# power_phase.net
KiCad netlist of a schematic drawn in Altium Designer
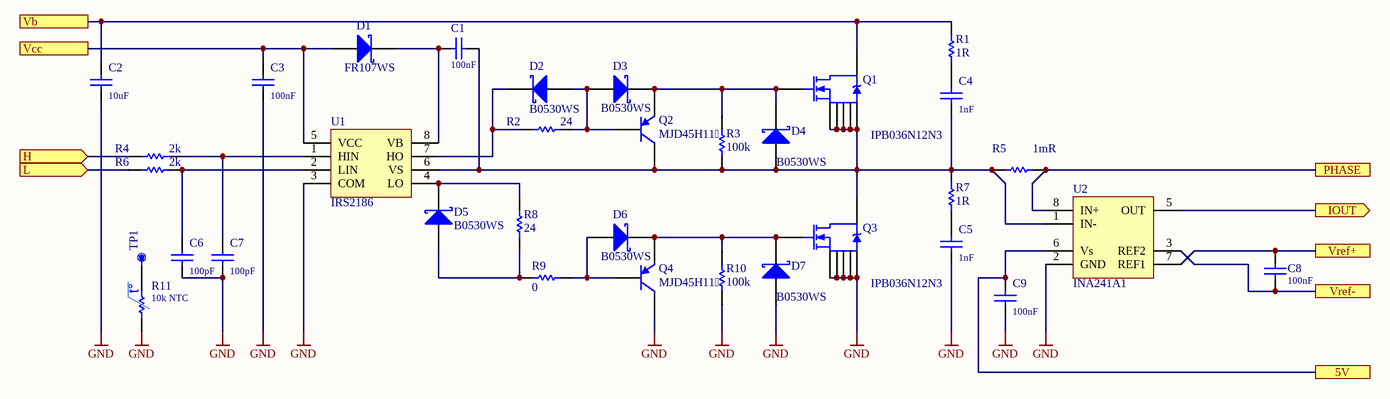
[diagram p0: power_phase.schdoc]

(export (version "E")
  (design (tool "Eeschema 10.0.6"))
  (components
    (comp (ref "C1")
      (value "100nF")
      (footprint "C0805_L")
      (description "100n 0805")
      (libsource (lib "Miscellaneous Devices") (part "CAP"))
    )
    (comp (ref "C2")
      (value "10uF")
      (footprint "C2220")
      (description "10uF 100V 2220")
      (libsource (lib "Miscellaneous Devices") (part "CAP"))
    )
    (comp (ref "C3")
      (value "100nF")
      (footprint "C0603")
      (description "100n 0603")
      (libsource (lib "Miscellaneous Devices") (part "CAP"))
    )
    (comp (ref "C4")
      (value "1nF")
      (footprint "C0805")
      (description "1nF 100V 0805")
      (libsource (lib "Miscellaneous Devices") (part "CAP"))
    )
    (comp (ref "C5")
      (value "1nF")
      (footprint "C0805")
      (description "1nF 100V 0805")
      (libsource (lib "Miscellaneous Devices") (part "CAP"))
    )
    (comp (ref "C6")
      (value "100pF")
      (footprint "C0402")
      (description "100pF 0402")
      (libsource (lib "Miscellaneous Devices") (part "CAP"))
    )
    (comp (ref "C7")
      (value "100pF")
      (footprint "C0402")
      (description "100pF 0402")
      (libsource (lib "Miscellaneous Devices") (part "CAP"))
    )
    (comp (ref "C8")
      (value "100nF")
      (footprint "C0402")
      (description "100nF 0402")
      (libsource (lib "Miscellaneous Devices") (part "CAP"))
    )
    (comp (ref "C9")
      (value "100nF")
      (footprint "C0402")
      (description "100nF 0402")
      (libsource (lib "Miscellaneous Devices") (part "CAP"))
    )
    (comp (ref "D1")
      (value "FR107WS")
      (footprint "SOD-323")
      (libsource (lib "Miscellaneous Devices") (part "Diode 10TQ035_1"))
    )
    (comp (ref "D2")
      (value "B0530WS")
      (footprint "SOD-323")
      (description "FR107WS")
      (libsource (lib "Miscellaneous Devices") (part "Diode 10TQ035_1"))
    )
    (comp (ref "D3")
      (value "B0530WS")
      (footprint "SOD-323")
      (description "FR107WS")
      (libsource (lib "Miscellaneous Devices") (part "Diode 10TQ035_1"))
    )
    (comp (ref "D4")
      (value "B0530WS")
      (footprint "SOD-323")
      (description "FR107WS")
      (libsource (lib "Miscellaneous Devices") (part "Diode 10TQ035_1"))
    )
    (comp (ref "D5")
      (value "B0530WS")
      (footprint "SOD-323")
      (description "FR107WS")
      (libsource (lib "Miscellaneous Devices") (part "Diode 10TQ035_1"))
    )
    (comp (ref "D6")
      (value "B0530WS")
      (footprint "SOD-323")
      (description "FR107WS")
      (libsource (lib "Miscellaneous Devices") (part "Diode 10TQ035_1"))
    )
    (comp (ref "D7")
      (value "B0530WS")
      (footprint "SOD-323")
      (description "FR107WS")
      (libsource (lib "Miscellaneous Devices") (part "Diode 10TQ035_1"))
    )
    (comp (ref "Q1")
      (value "IPB036N12N3")
      (footprint "TO-263-7")
      (description "IPB036N12N3GATMA1")
      (libsource (lib "Miscellaneous Devices") (part "NMOS-2"))
    )
    (comp (ref "Q2")
      (value "MJD45H11")
      (footprint "TO-252AA")
      (libsource (lib "Miscellaneous Devices") (part "PNP"))
    )
    (comp (ref "Q3")
      (value "IPB036N12N3")
      (footprint "TO-263-7")
      (description "IPB036N12N3GATMA1")
      (libsource (lib "Miscellaneous Devices") (part "NMOS-2"))
    )
    (comp (ref "Q4")
      (value "MJD45H11")
      (footprint "TO-252AA")
      (libsource (lib "Miscellaneous Devices") (part "PNP"))
    )
    (comp (ref "R1")
      (value "1R")
      (footprint "R1206")
      (description "1R 1206")
      (libsource (lib "Miscellaneous Devices") (part "Res1"))
    )
    (comp (ref "R2")
      (value "24")
      (footprint "R0603")
      (description "24R 0603")
      (libsource (lib "Miscellaneous Devices") (part "Res1"))
    )
    (comp (ref "R3")
      (value "100k")
      (footprint "R0805")
      (description "100k 0805")
      (libsource (lib "Miscellaneous Devices") (part "Res1"))
    )
    (comp (ref "R4")
      (value "2k")
      (footprint "R0603")
      (description "2k 0603")
      (libsource (lib "Miscellaneous Devices") (part "Res1"))
    )
    (comp (ref "R5")
      (value "1mR")
      (footprint "RES_CSS2H-3920R")
      (libsource (lib "Miscellaneous Devices") (part "Res1"))
    )
    (comp (ref "R6")
      (value "2k")
      (footprint "R0603")
      (description "2k 0603")
      (libsource (lib "Miscellaneous Devices") (part "Res1"))
    )
    (comp (ref "R7")
      (value "1R")
      (footprint "R1206")
      (description "1R 1206")
      (libsource (lib "Miscellaneous Devices") (part "Res1"))
    )
    (comp (ref "R8")
      (value "24")
      (footprint "R0603")
      (description "24R 0603")
      (libsource (lib "Miscellaneous Devices") (part "Res1"))
    )
    (comp (ref "R9")
      (value "0")
      (footprint "R1206")
      (description "0R 2512")
      (libsource (lib "Miscellaneous Devices") (part "Res1"))
    )
    (comp (ref "R10")
      (value "100k")
      (footprint "R0805")
      (description "100k 0805")
      (libsource (lib "Miscellaneous Devices") (part "Res1"))
    )
    (comp (ref "R11")
      (value "10k NTC")
      (footprint "R0402")
      (libsource (lib "Miscellaneous Devices") (part "RES"))
    )
    (comp (ref "TP1")
      (value "~")
      (footprint "TP2030_SMD")
      (libsource (lib "Miscellaneous Devices") (part "TP_Dup1"))
    )
    (comp (ref "U1")
      (value "IRS2186")
      (footprint "SO-8")
      (description "IR2186")
      (libsource (lib "Miscellaneous Devices") (part "IRS2186"))
    )
    (comp (ref "U2") (value "INA241A1") (footprint "SOT-23-8") (libsource (lib "Schlib1") (part "INA241A1")))
  )
  (nets
    (net (code "1") (name "/5V") (class "Default")
      (node (ref "C9") (pin "2") (pinfunction "2_2") (pintype "passive"))
      (node (ref "U2") (pin "6") (pinfunction "Vs_6") (pintype "passive"))
    )
    (net (code "2") (name "/H") (class "Default")
      (node (ref "R4") (pin "2") (pinfunction "2_2") (pintype "passive"))
    )
    (net (code "3") (name "/IOUT") (class "Default")
      (node (ref "U2") (pin "5") (pinfunction "OUT_5") (pintype "passive"))
    )
    (net (code "4") (name "/L") (class "Default")
      (node (ref "R6") (pin "2") (pinfunction "2_2") (pintype "passive"))
    )
    (net (code "5") (name "/PHASE") (class "Default")
      (node (ref "R5") (pin "2") (pinfunction "2_2") (pintype "passive"))
      (node (ref "U2") (pin "8") (pinfunction "IN+_8") (pintype "passive"))
    )
    (net (code "6") (name "/Vb") (class "Default")
      (node (ref "C2") (pin "2") (pinfunction "2_2") (pintype "passive"))
      (node (ref "Q1") (pin "4") (pinfunction "D_4") (pintype "passive"))
      (node (ref "R1") (pin "2") (pinfunction "2_2") (pintype "passive"))
    )
    (net (code "7") (name "/Vcc") (class "Default")
      (node (ref "C3") (pin "2") (pinfunction "2_2") (pintype "passive"))
      (node (ref "D1") (pin "1") (pinfunction "A_1") (pintype "passive"))
      (node (ref "U1") (pin "5") (pinfunction "VCC_5") (pintype "power_in"))
    )
    (net (code "8") (name "/Vref+") (class "Default")
      (node (ref "C8") (pin "2") (pinfunction "2_2") (pintype "passive"))
      (node (ref "U2") (pin "7") (pinfunction "REF1_7") (pintype "passive"))
    )
    (net (code "9") (name "/Vref-") (class "Default")
      (node (ref "C8") (pin "1") (pinfunction "1_1") (pintype "passive"))
      (node (ref "U2") (pin "3") (pinfunction "REF2_3") (pintype "passive"))
    )
    (net (code "10") (name "GND") (class "Default")
      (node (ref "C2") (pin "1") (pinfunction "1_1") (pintype "passive"))
      (node (ref "C3") (pin "1") (pinfunction "1_1") (pintype "passive"))
      (node (ref "C5") (pin "1") (pinfunction "1_1") (pintype "passive"))
      (node (ref "C6") (pin "1") (pinfunction "1_1") (pintype "passive"))
      (node (ref "C7") (pin "1") (pinfunction "1_1") (pintype "passive"))
      (node (ref "C9") (pin "1") (pinfunction "1_1") (pintype "passive"))
      (node (ref "D7") (pin "1") (pinfunction "A_1") (pintype "passive"))
      (node (ref "Q3") (pin "2") (pinfunction "S_2") (pintype "passive"))
      (node (ref "Q3") (pin "3") (pinfunction "S_3") (pintype "passive"))
      (node (ref "Q3") (pin "5") (pinfunction "S_5") (pintype "passive"))
      (node (ref "Q3") (pin "6") (pinfunction "S_6") (pintype "passive"))
      (node (ref "Q3") (pin "7") (pinfunction "S_7") (pintype "passive"))
      (node (ref "Q4") (pin "2") (pinfunction "C_2") (pintype "passive"))
      (node (ref "R10") (pin "2") (pinfunction "2_2") (pintype "passive"))
      (node (ref "R11") (pin "2") (pinfunction "2_2") (pintype "passive"))
      (node (ref "U1") (pin "3") (pinfunction "COM_3") (pintype "power_in"))
      (node (ref "U2") (pin "2") (pinfunction "GND_2") (pintype "passive"))
    )
    (net (code "11") (name "Net-(C4-Pad2)") (class "Default")
      (node (ref "C4") (pin "2") (pinfunction "2_2") (pintype "passive"))
      (node (ref "R1") (pin "1") (pinfunction "1_1") (pintype "passive"))
    )
    (net (code "12") (name "Net-(C5-Pad2)") (class "Default")
      (node (ref "C5") (pin "2") (pinfunction "2_2") (pintype "passive"))
      (node (ref "R7") (pin "1") (pinfunction "1_1") (pintype "passive"))
    )
    (net (code "13") (name "Net-(D1-K)") (class "Default")
      (node (ref "C1") (pin "1") (pinfunction "1_1") (pintype "passive"))
      (node (ref "D1") (pin "2") (pinfunction "K_2") (pintype "passive"))
      (node (ref "U1") (pin "8") (pinfunction "VB_8") (pintype "passive"))
    )
    (net (code "14") (name "Net-(D2-A)") (class "Default")
      (node (ref "D2") (pin "1") (pinfunction "A_1") (pintype "passive"))
      (node (ref "D3") (pin "1") (pinfunction "A_1") (pintype "passive"))
      (node (ref "Q2") (pin "1") (pinfunction "B_1") (pintype "passive"))
      (node (ref "R2") (pin "1") (pinfunction "1_1") (pintype "passive"))
    )
    (net (code "15") (name "Net-(D2-K)") (class "Default")
      (node (ref "D2") (pin "2") (pinfunction "K_2") (pintype "passive"))
      (node (ref "R2") (pin "2") (pinfunction "2_2") (pintype "passive"))
      (node (ref "U1") (pin "7") (pinfunction "HO_7") (pintype "passive"))
    )
    (net (code "16") (name "Net-(D3-K)") (class "Default")
      (node (ref "D3") (pin "2") (pinfunction "K_2") (pintype "passive"))
      (node (ref "D4") (pin "2") (pinfunction "K_2") (pintype "passive"))
      (node (ref "Q1") (pin "1") (pinfunction "G_1") (pintype "passive"))
      (node (ref "Q2") (pin "3") (pinfunction "E_3") (pintype "passive"))
      (node (ref "R3") (pin "1") (pinfunction "1_1") (pintype "passive"))
    )
    (net (code "17") (name "Net-(D4-A)") (class "Default")
      (node (ref "C1") (pin "2") (pinfunction "2_2") (pintype "passive"))
      (node (ref "C4") (pin "1") (pinfunction "1_1") (pintype "passive"))
      (node (ref "D4") (pin "1") (pinfunction "A_1") (pintype "passive"))
      (node (ref "Q1") (pin "2") (pinfunction "S_2") (pintype "passive"))
      (node (ref "Q1") (pin "3") (pinfunction "S_3") (pintype "passive"))
      (node (ref "Q1") (pin "5") (pinfunction "S_5") (pintype "passive"))
      (node (ref "Q1") (pin "6") (pinfunction "S_6") (pintype "passive"))
      (node (ref "Q1") (pin "7") (pinfunction "S_7") (pintype "passive"))
      (node (ref "Q2") (pin "2") (pinfunction "C_2") (pintype "passive"))
      (node (ref "Q3") (pin "4") (pinfunction "D_4") (pintype "passive"))
      (node (ref "R3") (pin "2") (pinfunction "2_2") (pintype "passive"))
      (node (ref "R5") (pin "1") (pinfunction "1_1") (pintype "passive"))
      (node (ref "R7") (pin "2") (pinfunction "2_2") (pintype "passive"))
      (node (ref "U1") (pin "6") (pinfunction "VS_6") (pintype "passive"))
      (node (ref "U2") (pin "1") (pinfunction "IN-_1") (pintype "passive"))
    )
    (net (code "18") (name "Net-(D5-A)") (class "Default")
      (node (ref "D5") (pin "1") (pinfunction "A_1") (pintype "passive"))
      (node (ref "R8") (pin "1") (pinfunction "1_1") (pintype "passive"))
      (node (ref "R9") (pin "2") (pinfunction "2_2") (pintype "passive"))
    )
    (net (code "19") (name "Net-(D5-K)") (class "Default")
      (node (ref "D5") (pin "2") (pinfunction "K_2") (pintype "passive"))
      (node (ref "R8") (pin "2") (pinfunction "2_2") (pintype "passive"))
      (node (ref "U1") (pin "4") (pinfunction "LO_4") (pintype "passive"))
    )
    (net (code "20") (name "Net-(D6-A)") (class "Default")
      (node (ref "D6") (pin "1") (pinfunction "A_1") (pintype "passive"))
      (node (ref "Q4") (pin "1") (pinfunction "B_1") (pintype "passive"))
      (node (ref "R9") (pin "1") (pinfunction "1_1") (pintype "passive"))
    )
    (net (code "21") (name "Net-(D6-K)") (class "Default")
      (node (ref "D6") (pin "2") (pinfunction "K_2") (pintype "passive"))
      (node (ref "D7") (pin "2") (pinfunction "K_2") (pintype "passive"))
      (node (ref "Q3") (pin "1") (pinfunction "G_1") (pintype "passive"))
      (node (ref "Q4") (pin "3") (pinfunction "E_3") (pintype "passive"))
      (node (ref "R10") (pin "1") (pinfunction "1_1") (pintype "passive"))
    )
    (net (code "22") (name "Net-(R11-Pad1)") (class "Default")
      (node (ref "R11") (pin "1") (pinfunction "1_1") (pintype "passive"))
      (node (ref "TP1") (pin "1") (pinfunction "1_1") (pintype "passive"))
    )
    (net (code "23") (name "Net-(U1-HIN)") (class "Default")
      (node (ref "C7") (pin "2") (pinfunction "2_2") (pintype "passive"))
      (node (ref "R4") (pin "1") (pinfunction "1_1") (pintype "passive"))
      (node (ref "U1") (pin "1") (pinfunction "HIN_1") (pintype "passive"))
    )
    (net (code "24") (name "Net-(U1-LIN)") (class "Default")
      (node (ref "C6") (pin "2") (pinfunction "2_2") (pintype "passive"))
      (node (ref "R6") (pin "1") (pinfunction "1_1") (pintype "passive"))
      (node (ref "U1") (pin "2") (pinfunction "LIN_2") (pintype "passive"))
    )
  )
)
